# RD01.net
KiCad netlist of a schematic drawn in EAGLE
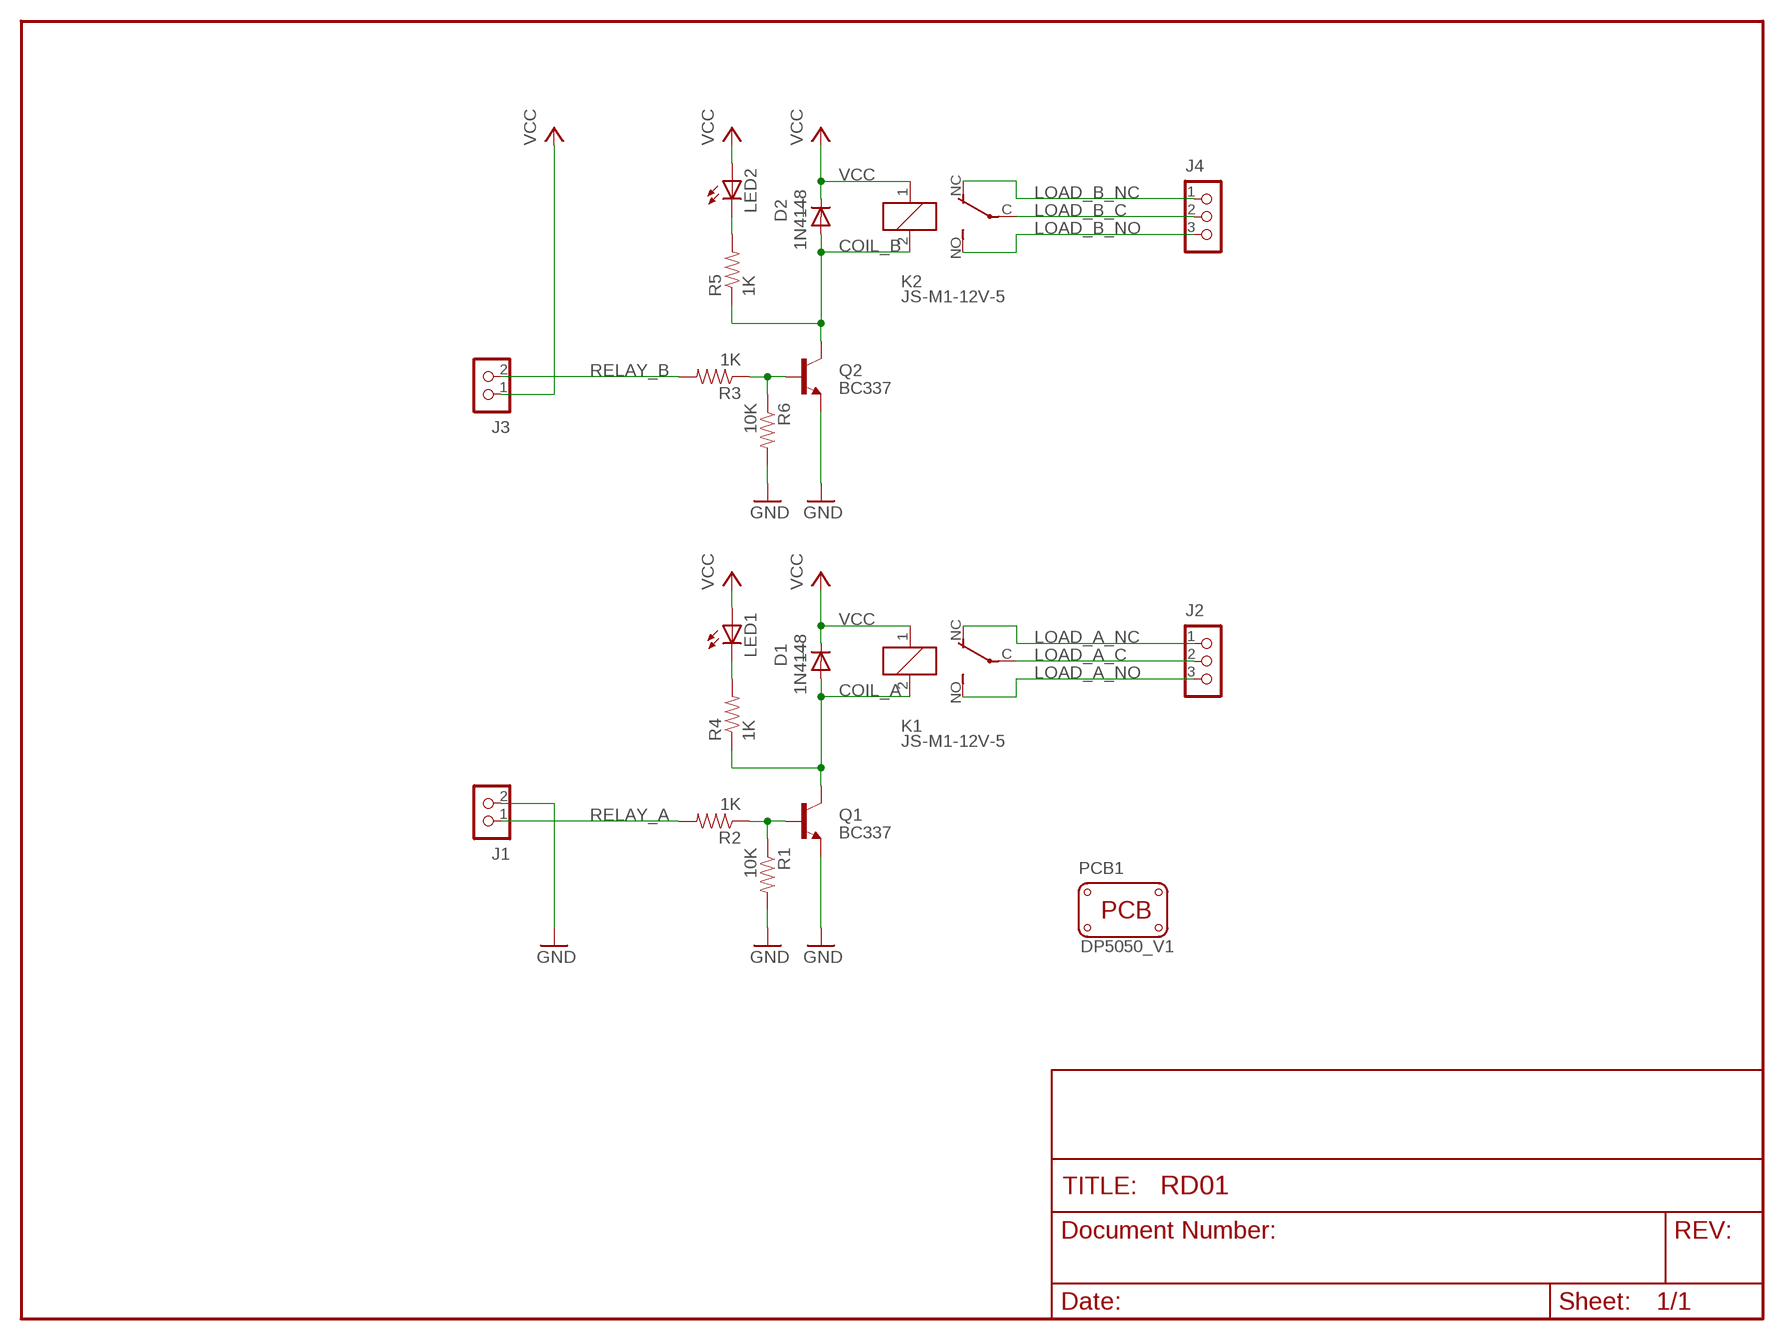
[diagram p0: schematic, sheet 1]

(export (version "E")
  (design (tool "Eeschema 10.0.6"))
  (components
    (comp (ref "D1")
      (value "1N4148")
      (footprint "eagle-import:DIODE-1N4148")
      (libsource (lib "eagle-import") (part "DIODE1N4148"))
    )
    (comp (ref "D2")
      (value "1N4148")
      (footprint "eagle-import:DIODE-1N4148")
      (libsource (lib "eagle-import") (part "DIODE1N4148"))
    )
    (comp (ref "J1")
      (value "CON_TERMINAL_BLOCK_02-5MM")
      (footprint "eagle-import:TERMINAL_BLOCK_2P_5")
      (libsource (lib "eagle-import") (part "CON_TERMINAL_BLOCK_02-5MM"))
    )
    (comp (ref "J2")
      (value "CON_TERMINAL_BLOCK_03-5MM")
      (footprint "eagle-import:TERMINAL_BLOCK_3P_5")
      (libsource (lib "eagle-import") (part "CON_TERMINAL_BLOCK_03-5MM"))
    )
    (comp (ref "J3")
      (value "CON_TERMINAL_BLOCK_02-5MM")
      (footprint "eagle-import:TERMINAL_BLOCK_2P_5")
      (libsource (lib "eagle-import") (part "CON_TERMINAL_BLOCK_02-5MM"))
    )
    (comp (ref "J4")
      (value "CON_TERMINAL_BLOCK_03-5MM")
      (footprint "eagle-import:TERMINAL_BLOCK_3P_5")
      (libsource (lib "eagle-import") (part "CON_TERMINAL_BLOCK_03-5MM"))
    )
    (comp (ref "K1")
      (value "JS-M1-12V-5")
      (footprint "eagle-import:JS-M")
      (fields
        (field (name "MF") "FARNELL")
        (field (name "MPN") "JSM1-12V-5")
        (field (name "MF_1") "FARNELL")
        (field (name "MPN_1") "JSM1-12V-5")
        (field (name "OC_FARNELL") "910351")
        (field (name "OC_NEWARK") "14J1764")
      )
      (libsource (lib "eagle-import") (part "JS-M1-12V-5"))
    )
    (comp (ref "K2")
      (value "JS-M1-12V-5")
      (footprint "eagle-import:JS-M")
      (fields
        (field (name "MF") "FARNELL")
        (field (name "MPN") "JSM1-12V-5")
        (field (name "MF_1") "FARNELL")
        (field (name "MPN_1") "JSM1-12V-5")
        (field (name "OC_FARNELL") "910351")
        (field (name "OC_NEWARK") "14J1764")
      )
      (libsource (lib "eagle-import") (part "JS-M1-12V-5"))
    )
    (comp (ref "LED1")
      (value "LED-3MM")
      (footprint "eagle-import:LED-3MM")
      (libsource (lib "eagle-import") (part "LED-3MM"))
    )
    (comp (ref "LED2")
      (value "LED-3MM")
      (footprint "eagle-import:LED-3MM")
      (libsource (lib "eagle-import") (part "LED-3MM"))
    )
    (comp (ref "PCB1")
      (value "PCB_DP_SQUARE-5X5")
      (footprint "eagle-import:DP5050_V1")
      (libsource (lib "eagle-import") (part "PCB_DP_SQUARE-5X5"))
    )
    (comp (ref "Q1")
      (value "BC337")
      (footprint "eagle-import:TO92")
      (libsource (lib "eagle-import") (part "BC337"))
    )
    (comp (ref "Q2")
      (value "BC337")
      (footprint "eagle-import:TO92")
      (libsource (lib "eagle-import") (part "BC337"))
    )
    (comp (ref "R1")
      (value "10K")
      (footprint "eagle-import:AXIAL-0.3")
      (libsource (lib "eagle-import") (part "RESISTORAXIAL-0.3"))
    )
    (comp (ref "R2")
      (value "1K")
      (footprint "eagle-import:AXIAL-0.3")
      (libsource (lib "eagle-import") (part "RESISTORAXIAL-0.3"))
    )
    (comp (ref "R3")
      (value "1K")
      (footprint "eagle-import:AXIAL-0.3")
      (libsource (lib "eagle-import") (part "RESISTORAXIAL-0.3"))
    )
    (comp (ref "R4")
      (value "1K")
      (footprint "eagle-import:AXIAL-0.3")
      (libsource (lib "eagle-import") (part "RESISTORAXIAL-0.3"))
    )
    (comp (ref "R5")
      (value "1K")
      (footprint "eagle-import:AXIAL-0.3")
      (libsource (lib "eagle-import") (part "RESISTORAXIAL-0.3"))
    )
    (comp (ref "R6")
      (value "10K")
      (footprint "eagle-import:AXIAL-0.3")
      (libsource (lib "eagle-import") (part "RESISTORAXIAL-0.3"))
    )
  )
  (nets
    (net (code "1") (name "/COIL_A") (class "Default")
      (node (ref "D1") (pin "A") (pinfunction "A_A") (pintype "passive"))
      (node (ref "K1") (pin "2") (pinfunction "2_2") (pintype "passive"))
      (node (ref "Q1") (pin "3") (pinfunction "C_3") (pintype "passive"))
      (node (ref "R4") (pin "P$1") (pinfunction "1_P$1") (pintype "passive"))
    )
    (net (code "2") (name "/COIL_B") (class "Default")
      (node (ref "D2") (pin "A") (pinfunction "A_A") (pintype "passive"))
      (node (ref "K2") (pin "2") (pinfunction "2_2") (pintype "passive"))
      (node (ref "Q2") (pin "3") (pinfunction "C_3") (pintype "passive"))
      (node (ref "R5") (pin "P$1") (pinfunction "1_P$1") (pintype "passive"))
    )
    (net (code "3") (name "/LOAD_A_C") (class "Default")
      (node (ref "J2") (pin "2") (pinfunction "2_2") (pintype "bidirectional"))
      (node (ref "K1") (pin "C") (pinfunction "P_C") (pintype "passive"))
    )
    (net (code "4") (name "/LOAD_A_NC") (class "Default")
      (node (ref "J2") (pin "1") (pinfunction "1_1") (pintype "bidirectional"))
      (node (ref "K1") (pin "NC") (pinfunction "O_NC") (pintype "passive"))
    )
    (net (code "5") (name "/LOAD_A_NO") (class "Default")
      (node (ref "J2") (pin "3") (pinfunction "3_3") (pintype "bidirectional"))
      (node (ref "K1") (pin "NO") (pinfunction "S_NO") (pintype "passive"))
    )
    (net (code "6") (name "/LOAD_B_C") (class "Default")
      (node (ref "J4") (pin "2") (pinfunction "2_2") (pintype "bidirectional"))
      (node (ref "K2") (pin "C") (pinfunction "P_C") (pintype "passive"))
    )
    (net (code "7") (name "/LOAD_B_NC") (class "Default")
      (node (ref "J4") (pin "1") (pinfunction "1_1") (pintype "bidirectional"))
      (node (ref "K2") (pin "NC") (pinfunction "O_NC") (pintype "passive"))
    )
    (net (code "8") (name "/LOAD_B_NO") (class "Default")
      (node (ref "J4") (pin "3") (pinfunction "3_3") (pintype "bidirectional"))
      (node (ref "K2") (pin "NO") (pinfunction "S_NO") (pintype "passive"))
    )
    (net (code "9") (name "/RELAY_A") (class "Default")
      (node (ref "J1") (pin "1") (pinfunction "1_1") (pintype "passive"))
      (node (ref "R2") (pin "P$2") (pinfunction "2_P$2") (pintype "passive"))
    )
    (net (code "10") (name "/RELAY_B") (class "Default")
      (node (ref "J3") (pin "2") (pinfunction "2_2") (pintype "passive"))
      (node (ref "R3") (pin "P$2") (pinfunction "2_P$2") (pintype "passive"))
    )
    (net (code "11") (name "GND") (class "Default")
      (node (ref "J1") (pin "2") (pinfunction "2_2") (pintype "passive"))
      (node (ref "Q1") (pin "1") (pinfunction "E_1") (pintype "passive"))
      (node (ref "Q2") (pin "1") (pinfunction "E_1") (pintype "passive"))
      (node (ref "R1") (pin "P$2") (pinfunction "2_P$2") (pintype "passive"))
      (node (ref "R6") (pin "P$2") (pinfunction "2_P$2") (pintype "passive"))
    )
    (net (code "12") (name "Net-(LED1-C)") (class "Default")
      (node (ref "LED1") (pin "K") (pinfunction "C_K") (pintype "passive"))
      (node (ref "R4") (pin "P$2") (pinfunction "2_P$2") (pintype "passive"))
    )
    (net (code "13") (name "Net-(LED2-C)") (class "Default")
      (node (ref "LED2") (pin "K") (pinfunction "C_K") (pintype "passive"))
      (node (ref "R5") (pin "P$2") (pinfunction "2_P$2") (pintype "passive"))
    )
    (net (code "14") (name "Net-(Q1-B)") (class "Default")
      (node (ref "Q1") (pin "2") (pinfunction "B_2") (pintype "passive"))
      (node (ref "R1") (pin "P$1") (pinfunction "1_P$1") (pintype "passive"))
      (node (ref "R2") (pin "P$1") (pinfunction "1_P$1") (pintype "passive"))
    )
    (net (code "15") (name "Net-(Q2-B)") (class "Default")
      (node (ref "Q2") (pin "2") (pinfunction "B_2") (pintype "passive"))
      (node (ref "R3") (pin "P$1") (pinfunction "1_P$1") (pintype "passive"))
      (node (ref "R6") (pin "P$1") (pinfunction "1_P$1") (pintype "passive"))
    )
    (net (code "16") (name "VCC") (class "Default")
      (node (ref "D1") (pin "C") (pinfunction "C_C") (pintype "passive"))
      (node (ref "D2") (pin "C") (pinfunction "C_C") (pintype "passive"))
      (node (ref "J3") (pin "1") (pinfunction "1_1") (pintype "passive"))
      (node (ref "K1") (pin "1") (pinfunction "1_1") (pintype "passive"))
      (node (ref "K2") (pin "1") (pinfunction "1_1") (pintype "passive"))
      (node (ref "LED1") (pin "A") (pinfunction "A_A") (pintype "passive"))
      (node (ref "LED2") (pin "A") (pinfunction "A_A") (pintype "passive"))
    )
  )
)
